# POWER.net
KiCad netlist of a schematic drawn in Altium Designer
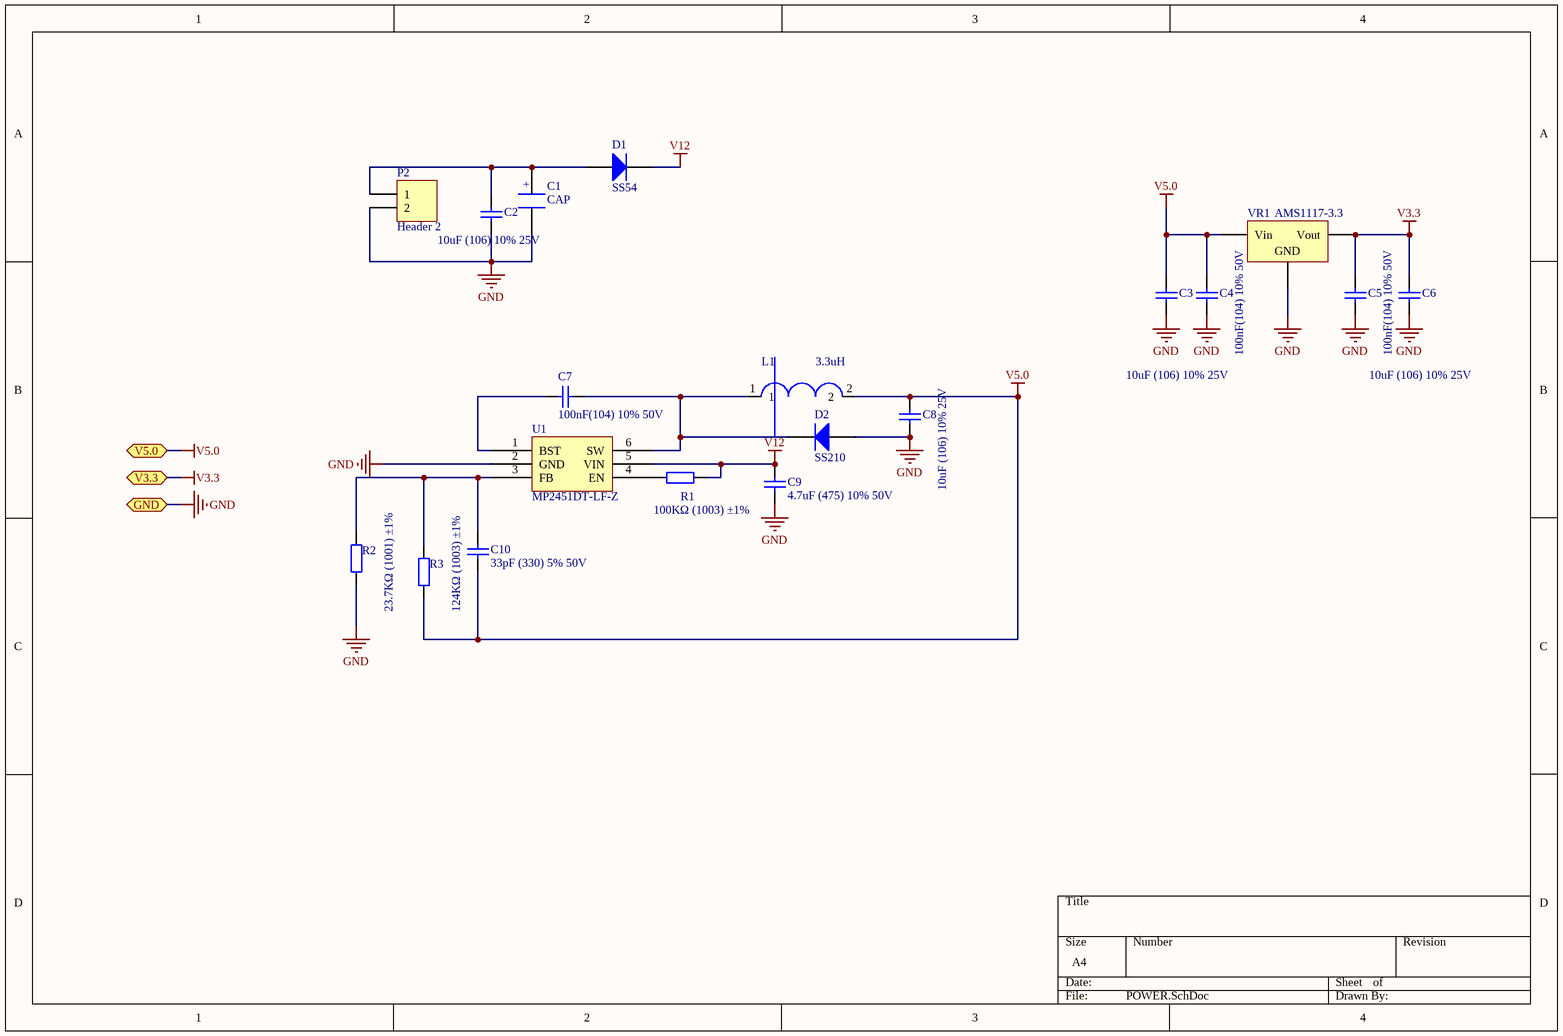
[diagram p0: POWER.SchDoc]

(export (version "E")
  (design (tool "Eeschema 10.0.6"))
  (components
    (comp (ref "C1") (value "CAP") (footprint "8X12_CAP") (libsource (lib "mylib") (part "CAP")))
    (comp (ref "C2")
      (value "10uF (106) 10% 25V")
      (footprint "0805_C")
      (description "贴片电容")
      (libsource (lib "Miscellaneous Devices LC") (part "0805 10uF (106) 10% 25V"))
    )
    (comp (ref "C3")
      (value "10uF (106) 10% 25V")
      (footprint "0805_C")
      (description "贴片电容")
      (libsource (lib "Miscellaneous Devices LC") (part "0805 10uF (106) 10% 25V"))
    )
    (comp (ref "C4")
      (value "100nF(104) 10% 50V")
      (footprint "0805_C")
      (description "贴片电容")
      (libsource (lib "Miscellaneous Devices LC") (part "0805 100nF(104) 10% 50V"))
    )
    (comp (ref "C5")
      (value "100nF(104) 10% 50V")
      (footprint "0805_C")
      (description "贴片电容")
      (libsource (lib "Miscellaneous Devices LC") (part "0805 100nF(104) 10% 50V"))
    )
    (comp (ref "C6")
      (value "10uF (106) 10% 25V")
      (footprint "0805_C")
      (description "贴片电容")
      (libsource (lib "Miscellaneous Devices LC") (part "0805 10uF (106) 10% 25V"))
    )
    (comp (ref "C7")
      (value "100nF(104) 10% 50V")
      (footprint "0805_C")
      (description "贴片电容")
      (libsource (lib "Miscellaneous Devices LC") (part "0805 100nF(104) 10% 50V"))
    )
    (comp (ref "C8")
      (value "10uF (106) 10% 25V")
      (footprint "0805_C")
      (description "贴片电容")
      (libsource (lib "Miscellaneous Devices LC") (part "0805 10uF (106) 10% 25V"))
    )
    (comp (ref "C9")
      (value "4.7uF (475) 10% 50V")
      (footprint "1206_C")
      (description "贴片电容")
      (libsource (lib "Miscellaneous Devices LC") (part "1206 4.7uF (475) 10% 50V"))
    )
    (comp (ref "C10")
      (value "33pF (330) 5% 50V")
      (footprint "0805_C")
      (description "贴片电容")
      (libsource (lib "Miscellaneous Devices LC") (part "0805 33pF (330) 5% 50V"))
    )
    (comp (ref "D1")
      (value "SS54")
      (footprint "SMA(DO-214AC)_S1")
      (description "二极管")
      (libsource (lib "Miscellaneous Devices LC") (part "SMA(DO-214AC) SS54"))
    )
    (comp (ref "D2")
      (value "SS210")
      (footprint "SMA(DO-214AC)_S1")
      (description "二极管")
      (libsource (lib "Miscellaneous Devices LC") (part "SMA(DO-214AC) SS210"))
    )
    (comp (ref "L1") (value "3.3uH") (footprint "L_4030") (libsource (lib "mylib") (part "33uH")))
    (comp (ref "P2")
      (value "Header 2")
      (footprint "WJ25")
      (description "Header, 2-Pin")
      (fields (field (name "PUBLISHER") "Altium Limited"))
      (libsource (lib "Miscellaneous Connectors") (part "Header 2"))
    )
    (comp (ref "R1")
      (value "100KΩ (1003) ±1%")
      (footprint "0805_R")
      (description "贴片电阻")
      (libsource (lib "") (part "0805 100KΩ (1003) 1%_1"))
    )
    (comp (ref "R2")
      (value "23.7KΩ (1001) ±1%")
      (footprint "0805_R")
      (description "贴片电阻")
      (libsource (lib "Miscellaneous Devices LC") (part "0805 1KΩ (1001) 1%"))
    )
    (comp (ref "R3")
      (value "124KΩ (1003) ±1%")
      (footprint "0805_R")
      (description "贴片电阻")
      (libsource (lib "Miscellaneous Devices LC") (part "0805 100KΩ (1003) 1%"))
    )
    (comp (ref "U1")
      (value "MP2451DT-LF-Z")
      (footprint "SOT-23-6")
      (description "DC-DC芯片")
      (libsource (lib "Miscellaneous Devices LC") (part "MP2451DT-LF-Z_[C14123]"))
    )
    (comp (ref "VR1")
      (value "AMS1117-3.3")
      (footprint "SOT-223")
      (description "低压差线性稳压(LDO)")
      (libsource (lib "Miscellaneous Devices LC") (part "SOT-223 AMS1117-3.3"))
    )
  )
  (nets
    (net (code "1") (name "GND") (class "Default")
      (node (ref "C1") (pin "2") (pinfunction "2_2") (pintype "passive"))
      (node (ref "C2") (pin "1") (pinfunction "1_1") (pintype "passive"))
      (node (ref "C3") (pin "1") (pinfunction "1_1") (pintype "passive"))
      (node (ref "C4") (pin "1") (pinfunction "1_1") (pintype "passive"))
      (node (ref "C5") (pin "1") (pinfunction "1_1") (pintype "passive"))
      (node (ref "C6") (pin "1") (pinfunction "1_1") (pintype "passive"))
      (node (ref "C8") (pin "1") (pinfunction "1_1") (pintype "passive"))
      (node (ref "C9") (pin "1") (pinfunction "1_1") (pintype "passive"))
      (node (ref "D2") (pin "1") (pinfunction "A_1") (pintype "passive"))
      (node (ref "P2") (pin "2") (pinfunction "2_2") (pintype "passive"))
      (node (ref "R2") (pin "1") (pinfunction "1_1") (pintype "passive"))
      (node (ref "U1") (pin "2") (pinfunction "GND_2") (pintype "passive"))
      (node (ref "VR1") (pin "1") (pinfunction "GND_1") (pintype "passive"))
    )
    (net (code "2") (name "Net-(D1-A)") (class "Default")
      (node (ref "C1") (pin "1") (pinfunction "1_1") (pintype "passive"))
      (node (ref "C2") (pin "2") (pinfunction "2_2") (pintype "passive"))
      (node (ref "D1") (pin "1") (pinfunction "A_1") (pintype "passive"))
      (node (ref "P2") (pin "1") (pinfunction "1_1") (pintype "passive"))
    )
    (net (code "3") (name "Net-(D2-K)") (class "Default")
      (node (ref "C7") (pin "1") (pinfunction "1_1") (pintype "passive"))
      (node (ref "D2") (pin "2") (pinfunction "K_2") (pintype "passive"))
      (node (ref "L1") (pin "1") (pinfunction "1_1") (pintype "passive"))
      (node (ref "U1") (pin "6") (pinfunction "SW_6") (pintype "passive"))
    )
    (net (code "4") (name "Net-(U1-BST)") (class "Default")
      (node (ref "C7") (pin "2") (pinfunction "2_2") (pintype "passive"))
      (node (ref "U1") (pin "1") (pinfunction "BST_1") (pintype "passive"))
    )
    (net (code "5") (name "Net-(U1-EN)") (class "Default")
      (node (ref "R1") (pin "2") (pinfunction "2_2") (pintype "passive"))
      (node (ref "U1") (pin "4") (pinfunction "EN_4") (pintype "passive"))
    )
    (net (code "6") (name "Net-(U1-FB)") (class "Default")
      (node (ref "C10") (pin "2") (pinfunction "2_2") (pintype "passive"))
      (node (ref "R2") (pin "2") (pinfunction "2_2") (pintype "passive"))
      (node (ref "R3") (pin "2") (pinfunction "2_2") (pintype "passive"))
      (node (ref "U1") (pin "3") (pinfunction "FB_3") (pintype "passive"))
    )
    (net (code "7") (name "V3.3") (class "Default")
      (node (ref "C5") (pin "2") (pinfunction "2_2") (pintype "passive"))
      (node (ref "C6") (pin "2") (pinfunction "2_2") (pintype "passive"))
      (node (ref "VR1") (pin "2") (pinfunction "Vout_2") (pintype "passive"))
    )
    (net (code "8") (name "V5.0") (class "Default")
      (node (ref "C10") (pin "1") (pinfunction "1_1") (pintype "passive"))
      (node (ref "C3") (pin "2") (pinfunction "2_2") (pintype "passive"))
      (node (ref "C4") (pin "2") (pinfunction "2_2") (pintype "passive"))
      (node (ref "C8") (pin "2") (pinfunction "2_2") (pintype "passive"))
      (node (ref "L1") (pin "2") (pinfunction "2_2") (pintype "passive"))
      (node (ref "R3") (pin "1") (pinfunction "1_1") (pintype "passive"))
      (node (ref "VR1") (pin "3") (pinfunction "Vin_3") (pintype "passive"))
    )
    (net (code "9") (name "V12") (class "Default")
      (node (ref "C9") (pin "2") (pinfunction "2_2") (pintype "passive"))
      (node (ref "D1") (pin "2") (pinfunction "K_2") (pintype "passive"))
      (node (ref "R1") (pin "1") (pinfunction "1_1") (pintype "passive"))
      (node (ref "U1") (pin "5") (pinfunction "VIN_5") (pintype "passive"))
    )
  )
)
